# Current_Sense_Amp.net
KiCad netlist of a schematic drawn in Altium Designer
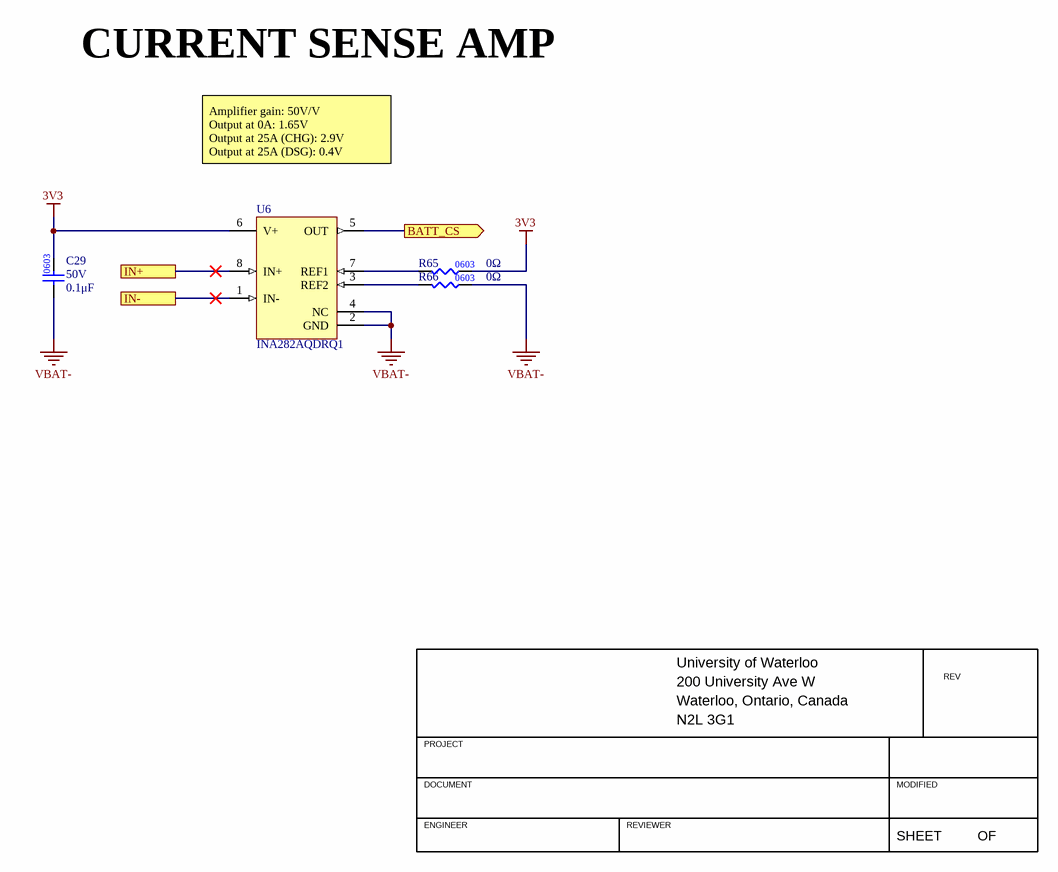
[diagram p0: Current_Sense_Amp.SchDoc]

(export (version "E")
  (design (tool "Eeschema 10.0.6"))
  (components
    (comp (ref "C29")
      (value "0.1μF")
      (footprint "CAP0603")
      (description "CAP CER 0.1UF 50V X7R 0603")
      (fields (field (name "VOLTAGE RATING") "50V") (field (name "Comment") "CAP_0.1uF_50V_0603"))
      (libsource (lib "Personal_Schematic_Library_2022") (part "CAP_0.1uF_50V_0603"))
    )
    (comp (ref "R65")
      (value "0Ω")
      (footprint "RES0603")
      (description "RES 0 OHM JUMPER 1/10W 0603")
      (fields (field (name "Comment") "RES_0Ω_0603"))
      (libsource (lib "Personal_Schematic_Library_2022") (part "RES_0Ω_0603"))
    )
    (comp (ref "R66")
      (value "0Ω")
      (footprint "RES0603")
      (description "RES 0 OHM JUMPER 1/10W 0603")
      (fields (field (name "Comment") "RES_0Ω_0603"))
      (libsource (lib "Personal_Schematic_Library_2022") (part "RES_0Ω_0603"))
    )
    (comp (ref "U6")
      (value "INA282AQDRQ1")
      (footprint "8-SOIC_M")
      (description "IC CURRENT MONITOR 0.4% 8SOIC")
      (fields (field (name "MANUFACTURER PART NUMBER 1") "INA282AQDRQ1"))
      (libsource (lib "Personal_Schematic_Library_2022") (part "INA282AQDRQ1"))
    )
  )
  (nets
    (net (code "1") (name "/BATT_CS") (class "Default")
      (node (ref "U6") (pin "5") (pinfunction "OUT_5") (pintype "output"))
    )
    (net (code "2") (name "/IN+") (class "Default")
      (node (ref "U6") (pin "8") (pinfunction "IN+_8") (pintype "input"))
    )
    (net (code "3") (name "/IN-") (class "Default")
      (node (ref "U6") (pin "1") (pinfunction "IN-_1") (pintype "input"))
    )
    (net (code "4") (name "3V3") (class "Default")
      (node (ref "C29") (pin "2") (pinfunction "2_2") (pintype "passive"))
      (node (ref "R65") (pin "2") (pinfunction "2_2") (pintype "passive"))
      (node (ref "U6") (pin "6") (pinfunction "V+_6") (pintype "power_in"))
    )
    (net (code "5") (name "Net-(U6-REF1)") (class "Default")
      (node (ref "R65") (pin "1") (pinfunction "1_1") (pintype "passive"))
      (node (ref "U6") (pin "7") (pinfunction "REF1_7") (pintype "input"))
    )
    (net (code "6") (name "Net-(U6-REF2)") (class "Default")
      (node (ref "R66") (pin "1") (pinfunction "1_1") (pintype "passive"))
      (node (ref "U6") (pin "3") (pinfunction "REF2_3") (pintype "input"))
    )
    (net (code "7") (name "VBAT-") (class "Default")
      (node (ref "C29") (pin "1") (pinfunction "1_1") (pintype "passive"))
      (node (ref "R66") (pin "2") (pinfunction "2_2") (pintype "passive"))
      (node (ref "U6") (pin "2") (pinfunction "GND_2") (pintype "passive"))
      (node (ref "U6") (pin "4") (pinfunction "NC_4") (pintype "passive"))
    )
  )
)
